# hw3_pcb.net
KiCad netlist of a schematic drawn in EAGLE
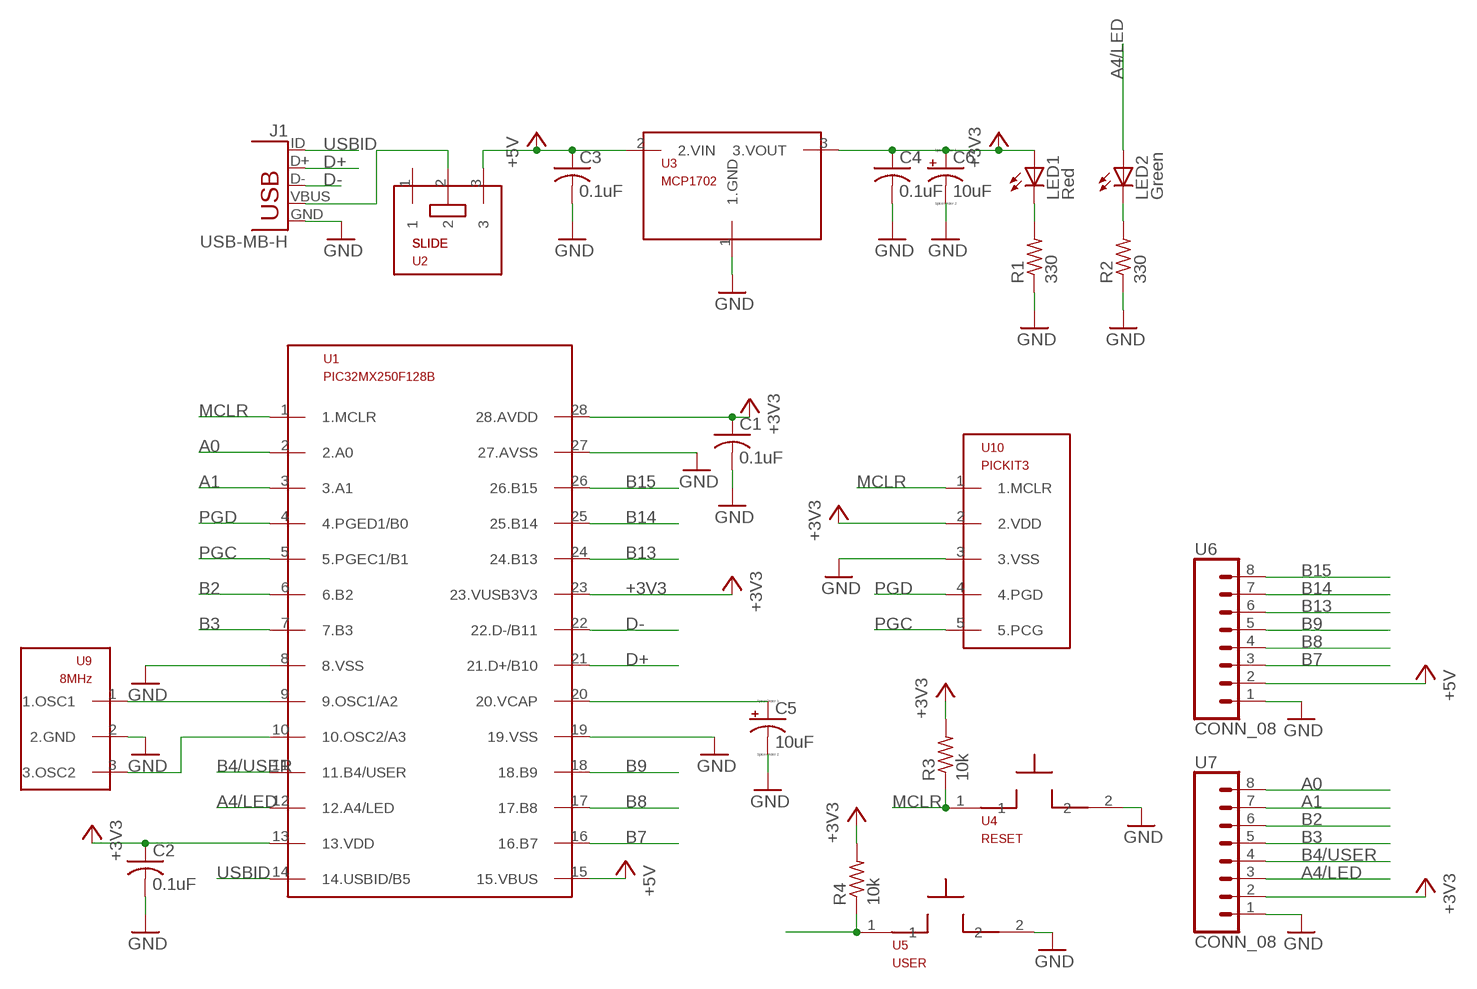
[diagram p0: schematic, sheet 1]

(export (version "E")
  (design (tool "Eeschema 10.0.6"))
  (components
    (comp (ref "C1")
      (value "0.1uF")
      (footprint "eagle-import:C025-025X050")
      (libsource (lib "eagle-import") (part "C-US025-025X050"))
    )
    (comp (ref "C2")
      (value "0.1uF")
      (footprint "eagle-import:C025-025X050")
      (libsource (lib "eagle-import") (part "C-US025-025X050"))
    )
    (comp (ref "C3")
      (value "0.1uF")
      (footprint "eagle-import:C025-025X050")
      (libsource (lib "eagle-import") (part "C-US025-025X050"))
    )
    (comp (ref "C4")
      (value "0.1uF")
      (footprint "eagle-import:C025-025X050")
      (libsource (lib "eagle-import") (part "C-US025-025X050"))
    )
    (comp (ref "C5")
      (value "10uF")
      (footprint "eagle-import:B45181B")
      (libsource (lib "eagle-import") (part "CPOL-USB45181B"))
    )
    (comp (ref "C6")
      (value "10uF")
      (footprint "eagle-import:B45181B")
      (libsource (lib "eagle-import") (part "CPOL-USB45181B"))
    )
    (comp (ref "J1")
      (value "USB-MB-H")
      (footprint "eagle-import:USB-MB-H")
      (libsource (lib "eagle-import") (part "USB-MB-H"))
    )
    (comp (ref "LED1")
      (value "Red")
      (footprint "eagle-import:LED3MM")
      (libsource (lib "eagle-import") (part "LED3MM"))
    )
    (comp (ref "LED2")
      (value "Green")
      (footprint "eagle-import:LED3MM")
      (libsource (lib "eagle-import") (part "LED3MM"))
    )
    (comp (ref "R1")
      (value "330")
      (footprint "eagle-import:0207_10")
      (libsource (lib "eagle-import") (part "R-US_0207/10"))
    )
    (comp (ref "R2")
      (value "330")
      (footprint "eagle-import:0207_10")
      (libsource (lib "eagle-import") (part "R-US_0207/10"))
    )
    (comp (ref "R3")
      (value "10k")
      (footprint "eagle-import:0207_10")
      (libsource (lib "eagle-import") (part "R-US_0207/10"))
    )
    (comp (ref "R4")
      (value "10k")
      (footprint "eagle-import:0207_10")
      (libsource (lib "eagle-import") (part "R-US_0207/10"))
    )
    (comp (ref "U1")
      (value "PIC32MX250F128B")
      (footprint "eagle-import:DIL28-3")
      (libsource (lib "eagle-import") (part "PIC32MX250F128B"))
    )
    (comp (ref "U2")
      (value "SLIDE")
      (footprint "eagle-import:SLIDE")
      (libsource (lib "eagle-import") (part "SLIDE"))
    )
    (comp (ref "U3")
      (value "MCP1702")
      (footprint "eagle-import:TO92")
      (libsource (lib "eagle-import") (part "MCP1702"))
    )
    (comp (ref "U4")
      (value "RESET")
      (footprint "eagle-import:PB")
      (libsource (lib "eagle-import") (part "PB"))
    )
    (comp (ref "U5")
      (value "USER")
      (footprint "eagle-import:PB")
      (libsource (lib "eagle-import") (part "PB"))
    )
    (comp (ref "U6")
      (value "CONN_08")
      (footprint "eagle-import:1X08")
      (libsource (lib "eagle-import") (part "CONN_08"))
    )
    (comp (ref "U7")
      (value "CONN_08")
      (footprint "eagle-import:1X08")
      (libsource (lib "eagle-import") (part "CONN_08"))
    )
    (comp (ref "U9")
      (value "8MHz")
      (footprint "eagle-import:OSC")
      (libsource (lib "eagle-import") (part "OSC"))
    )
    (comp (ref "U10")
      (value "PICKIT3")
      (footprint "eagle-import:1X05")
      (libsource (lib "eagle-import") (part "PICKIT3"))
    )
  )
  (nets
    (net (code "1") (name "+3V3") (class "Default")
      (node (ref "C1") (pin "1") (pinfunction "1_1") (pintype "passive"))
      (node (ref "C2") (pin "1") (pinfunction "1_1") (pintype "passive"))
      (node (ref "C4") (pin "1") (pinfunction "1_1") (pintype "passive"))
      (node (ref "C6") (pin "+") (pinfunction "+_+") (pintype "passive"))
      (node (ref "LED1") (pin "A") (pinfunction "A_A") (pintype "passive"))
      (node (ref "R3") (pin "2") (pinfunction "2_2") (pintype "passive"))
      (node (ref "R4") (pin "2") (pinfunction "2_2") (pintype "passive"))
      (node (ref "U1") (pin "13") (pinfunction "13.VDD_13") (pintype "bidirectional"))
      (node (ref "U1") (pin "23") (pinfunction "23.VUSB3V3_23") (pintype "bidirectional"))
      (node (ref "U1") (pin "28") (pinfunction "28.AVDD_28") (pintype "bidirectional"))
      (node (ref "U10") (pin "2") (pinfunction "2.VDD_2") (pintype "bidirectional"))
      (node (ref "U3") (pin "3") (pinfunction "3.VOUT_3") (pintype "bidirectional"))
      (node (ref "U7") (pin "2") (pinfunction "2_2") (pintype "passive"))
    )
    (net (code "2") (name "+5V") (class "Default")
      (node (ref "C3") (pin "1") (pinfunction "1_1") (pintype "passive"))
      (node (ref "U1") (pin "15") (pinfunction "15.VBUS_15") (pintype "bidirectional"))
      (node (ref "U2") (pin "3") (pinfunction "3_3") (pintype "bidirectional"))
      (node (ref "U3") (pin "2") (pinfunction "2.VIN_2") (pintype "bidirectional"))
      (node (ref "U6") (pin "2") (pinfunction "2_2") (pintype "passive"))
    )
    (net (code "3") (name "/A0") (class "Default")
      (node (ref "U1") (pin "2") (pinfunction "2.A0_2") (pintype "bidirectional"))
      (node (ref "U7") (pin "8") (pinfunction "8_8") (pintype "passive"))
    )
    (net (code "4") (name "/A1") (class "Default")
      (node (ref "U1") (pin "3") (pinfunction "3.A1_3") (pintype "bidirectional"))
      (node (ref "U7") (pin "7") (pinfunction "7_7") (pintype "passive"))
    )
    (net (code "5") (name "/A4{slash}LED") (class "Default")
      (node (ref "LED2") (pin "A") (pinfunction "A_A") (pintype "passive"))
      (node (ref "U1") (pin "12") (pinfunction "12.A4/LED_12") (pintype "bidirectional"))
      (node (ref "U7") (pin "3") (pinfunction "3_3") (pintype "passive"))
    )
    (net (code "6") (name "/B2") (class "Default")
      (node (ref "U1") (pin "6") (pinfunction "6.B2_6") (pintype "bidirectional"))
      (node (ref "U7") (pin "6") (pinfunction "6_6") (pintype "passive"))
    )
    (net (code "7") (name "/B3") (class "Default")
      (node (ref "U1") (pin "7") (pinfunction "7.B3_7") (pintype "bidirectional"))
      (node (ref "U7") (pin "5") (pinfunction "5_5") (pintype "passive"))
    )
    (net (code "8") (name "/B4{slash}USER") (class "Default")
      (node (ref "R4") (pin "1") (pinfunction "1_1") (pintype "passive"))
      (node (ref "U1") (pin "11") (pinfunction "11.B4/USER_11") (pintype "bidirectional"))
      (node (ref "U5") (pin "1") (pinfunction "1_1") (pintype "bidirectional"))
      (node (ref "U7") (pin "4") (pinfunction "4_4") (pintype "passive"))
    )
    (net (code "9") (name "/B7") (class "Default")
      (node (ref "U1") (pin "16") (pinfunction "16.B7_16") (pintype "bidirectional"))
      (node (ref "U6") (pin "3") (pinfunction "3_3") (pintype "passive"))
    )
    (net (code "10") (name "/B8") (class "Default")
      (node (ref "U1") (pin "17") (pinfunction "17.B8_17") (pintype "bidirectional"))
      (node (ref "U6") (pin "4") (pinfunction "4_4") (pintype "passive"))
    )
    (net (code "11") (name "/B9") (class "Default")
      (node (ref "U1") (pin "18") (pinfunction "18.B9_18") (pintype "bidirectional"))
      (node (ref "U6") (pin "5") (pinfunction "5_5") (pintype "passive"))
    )
    (net (code "12") (name "/B13") (class "Default")
      (node (ref "U1") (pin "24") (pinfunction "24.B13_24") (pintype "bidirectional"))
      (node (ref "U6") (pin "6") (pinfunction "6_6") (pintype "passive"))
    )
    (net (code "13") (name "/B14") (class "Default")
      (node (ref "U1") (pin "25") (pinfunction "25.B14_25") (pintype "bidirectional"))
      (node (ref "U6") (pin "7") (pinfunction "7_7") (pintype "passive"))
    )
    (net (code "14") (name "/B15") (class "Default")
      (node (ref "U1") (pin "26") (pinfunction "26.B15_26") (pintype "bidirectional"))
      (node (ref "U6") (pin "8") (pinfunction "8_8") (pintype "passive"))
    )
    (net (code "15") (name "/D+") (class "Default")
      (node (ref "J1") (pin "D+") (pinfunction "D+_D+") (pintype "bidirectional"))
      (node (ref "U1") (pin "21") (pinfunction "21.D+/B10_21") (pintype "bidirectional"))
    )
    (net (code "16") (name "/D-") (class "Default")
      (node (ref "J1") (pin "D-") (pinfunction "D-_D-") (pintype "bidirectional"))
      (node (ref "U1") (pin "22") (pinfunction "22.D-/B11_22") (pintype "bidirectional"))
    )
    (net (code "17") (name "/MCLR") (class "Default")
      (node (ref "R3") (pin "1") (pinfunction "1_1") (pintype "passive"))
      (node (ref "U1") (pin "1") (pinfunction "1.MCLR_1") (pintype "bidirectional"))
      (node (ref "U10") (pin "1") (pinfunction "1.MCLR_1") (pintype "bidirectional"))
      (node (ref "U4") (pin "1") (pinfunction "1_1") (pintype "bidirectional"))
    )
    (net (code "18") (name "/PGC") (class "Default")
      (node (ref "U1") (pin "5") (pinfunction "5.PGEC1/B1_5") (pintype "bidirectional"))
      (node (ref "U10") (pin "5") (pinfunction "5.PCG_5") (pintype "bidirectional"))
    )
    (net (code "19") (name "/PGD") (class "Default")
      (node (ref "U1") (pin "4") (pinfunction "4.PGED1/B0_4") (pintype "bidirectional"))
      (node (ref "U10") (pin "4") (pinfunction "4.PGD_4") (pintype "bidirectional"))
    )
    (net (code "20") (name "/USBID") (class "Default")
      (node (ref "J1") (pin "ID") (pinfunction "ID_ID") (pintype "bidirectional"))
      (node (ref "U1") (pin "14") (pinfunction "14.USBID/B5_14") (pintype "bidirectional"))
    )
    (net (code "21") (name "GND") (class "Default")
      (node (ref "C1") (pin "2") (pinfunction "2_2") (pintype "passive"))
      (node (ref "C2") (pin "2") (pinfunction "2_2") (pintype "passive"))
      (node (ref "C3") (pin "2") (pinfunction "2_2") (pintype "passive"))
      (node (ref "C4") (pin "2") (pinfunction "2_2") (pintype "passive"))
      (node (ref "C5") (pin "-") (pinfunction "-_-") (pintype "passive"))
      (node (ref "C6") (pin "-") (pinfunction "-_-") (pintype "passive"))
      (node (ref "J1") (pin "GND") (pinfunction "GND_GND") (pintype "bidirectional"))
      (node (ref "R1") (pin "1") (pinfunction "1_1") (pintype "passive"))
      (node (ref "R2") (pin "1") (pinfunction "1_1") (pintype "passive"))
      (node (ref "U1") (pin "19") (pinfunction "19.VSS_19") (pintype "bidirectional"))
      (node (ref "U1") (pin "27") (pinfunction "27.AVSS_27") (pintype "bidirectional"))
      (node (ref "U1") (pin "8") (pinfunction "8.VSS_8") (pintype "bidirectional"))
      (node (ref "U10") (pin "3") (pinfunction "3.VSS_3") (pintype "bidirectional"))
      (node (ref "U3") (pin "1") (pinfunction "1.GND_1") (pintype "bidirectional"))
      (node (ref "U4") (pin "2") (pinfunction "2_2") (pintype "bidirectional"))
      (node (ref "U5") (pin "2") (pinfunction "2_2") (pintype "bidirectional"))
      (node (ref "U6") (pin "1") (pinfunction "1_1") (pintype "passive"))
      (node (ref "U7") (pin "1") (pinfunction "1_1") (pintype "passive"))
      (node (ref "U9") (pin "2") (pinfunction "2.GND_2") (pintype "bidirectional"))
    )
    (net (code "22") (name "Net-(J1-PadVBUS)") (class "Default")
      (node (ref "J1") (pin "VBUS") (pinfunction "VBUS_VBUS") (pintype "bidirectional"))
      (node (ref "U2") (pin "2") (pinfunction "2_2") (pintype "bidirectional"))
    )
    (net (code "23") (name "Net-(LED1-C)") (class "Default")
      (node (ref "LED1") (pin "K") (pinfunction "C_K") (pintype "passive"))
      (node (ref "R1") (pin "2") (pinfunction "2_2") (pintype "passive"))
    )
    (net (code "24") (name "Net-(LED2-C)") (class "Default")
      (node (ref "LED2") (pin "K") (pinfunction "C_K") (pintype "passive"))
      (node (ref "R2") (pin "2") (pinfunction "2_2") (pintype "passive"))
    )
    (net (code "25") (name "Net-(U1-9.OSC1{slash}A2)") (class "Default")
      (node (ref "U1") (pin "9") (pinfunction "9.OSC1/A2_9") (pintype "bidirectional"))
      (node (ref "U9") (pin "1") (pinfunction "1.OSC1_1") (pintype "bidirectional"))
    )
    (net (code "26") (name "Net-(U1-10.OSC2{slash}A3)") (class "Default")
      (node (ref "U1") (pin "10") (pinfunction "10.OSC2/A3_10") (pintype "bidirectional"))
      (node (ref "U9") (pin "3") (pinfunction "3.OSC2_3") (pintype "bidirectional"))
    )
    (net (code "27") (name "Net-(U1-20.VCAP)") (class "Default")
      (node (ref "C5") (pin "+") (pinfunction "+_+") (pintype "passive"))
      (node (ref "U1") (pin "20") (pinfunction "20.VCAP_20") (pintype "bidirectional"))
    )
    (net (code "28") (name "unconnected-(U2-Pad1)") (class "Default")
      (node (ref "U2") (pin "1") (pinfunction "1_1") (pintype "bidirectional"))
    )
  )
)
